# LT1962Room.net
KiCad netlist of a schematic drawn in Altium Designer
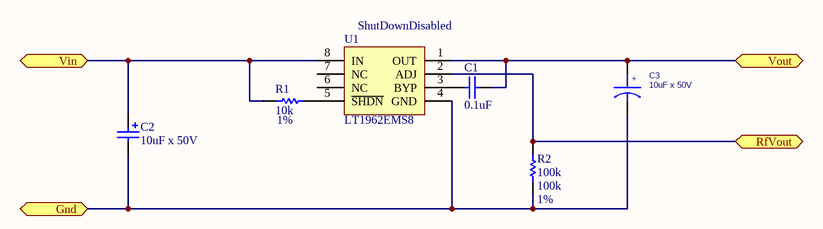
[diagram p0: LT1962Room.SchDoc]

(export (version "E")
  (design (tool "Eeschema 10.0.6"))
  (components
    (comp (ref "C1")
      (value "0.1uF")
      (footprint "0805")
      (description "Capacitor, Ceramic, 0603")
      (libsource (lib "AdamsParts") (part "Cap0603"))
    )
    (comp (ref "C2")
      (value "10uF x 50V")
      (footprint "CC4532-1812")
      (description "CAP POL C4532X5R1C336M")
      (fields (field (name "PUBLISHER") "Altium Limited"))
      (libsource (lib "Miscellaneous Devices") (part "Cap Pol3"))
    )
    (comp (ref "C3") (value "10uF x 50V") (libsource (lib "*") (part "CAP_POL")))
    (comp (ref "R1")
      (value "10k")
      (footprint "0805")
      (description "Resistor")
      (fields (field (name "PARAM") "1%"))
      (libsource (lib "AdamsParts") (part "Res0603"))
    )
    (comp (ref "R2")
      (value "100k")
      (footprint "0805")
      (description "Resistor")
      (fields (field (name "ALTIUM_VALUE") "100k") (field (name "PARAM") "1%"))
      (libsource (lib "AdamsParts") (part "Res0603"))
    )
    (comp (ref "U1")
      (value "LT1962EMS8")
      (footprint "MSOP-8")
      (description "micropower, low noise, low  dropout regulator")
      (libsource (lib "TEMPERATUREREADOUTSYSTEM2") (part "LT1962EMS8"))
    )
  )
  (nets
    (net (code "1") (name "/Gnd") (class "Default")
      (node (ref "C2") (pin "2") (pinfunction "2_2") (pintype "passive"))
      (node (ref "C3") (pin "2") (pinfunction "2_2") (pintype "passive"))
      (node (ref "R2") (pin "1") (pinfunction "1_1") (pintype "passive"))
      (node (ref "U1") (pin "4") (pinfunction "GND_4") (pintype "power_in"))
    )
    (net (code "2") (name "/RfVout") (class "Default")
      (node (ref "R2") (pin "2") (pinfunction "2_2") (pintype "passive"))
      (node (ref "U1") (pin "2") (pinfunction "ADJ_2") (pintype "passive"))
    )
    (net (code "3") (name "/Vin") (class "Default")
      (node (ref "C2") (pin "1") (pinfunction "1_1") (pintype "passive"))
      (node (ref "R1") (pin "2") (pinfunction "2_2") (pintype "passive"))
      (node (ref "U1") (pin "8") (pinfunction "IN_8") (pintype "passive"))
    )
    (net (code "4") (name "/Vout") (class "Default")
      (node (ref "C1") (pin "2") (pinfunction "2_2") (pintype "passive"))
      (node (ref "C3") (pin "1") (pinfunction "1_1") (pintype "passive"))
      (node (ref "U1") (pin "1") (pinfunction "OUT_1") (pintype "passive"))
    )
    (net (code "5") (name "Net-(U1-BYP)") (class "Default")
      (node (ref "C1") (pin "1") (pinfunction "1_1") (pintype "passive"))
      (node (ref "U1") (pin "3") (pinfunction "BYP_3") (pintype "passive"))
    )
    (net (code "6") (name "Net-(U1-~{SHDN})") (class "Default")
      (node (ref "R1") (pin "1") (pinfunction "1_1") (pintype "passive"))
      (node (ref "U1") (pin "5") (pinfunction "~{SHDN}_5") (pintype "passive"))
    )
    (net (code "7") (name "unconnected-(U1-NC-Pad6)") (class "Default")
      (node (ref "U1") (pin "6") (pinfunction "NC_6") (pintype "passive"))
    )
    (net (code "8") (name "unconnected-(U1-NC-Pad7)") (class "Default")
      (node (ref "U1") (pin "7") (pinfunction "NC_7") (pintype "passive"))
    )
  )
)
